# design.net
KiCad netlist of a schematic drawn in Altium Designer
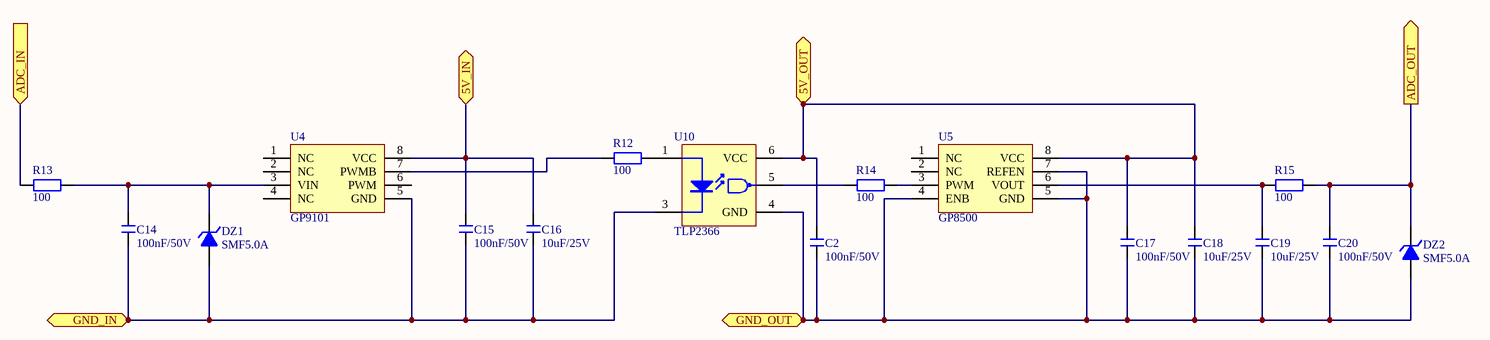
[diagram p0: 第一路电压隔离原理图.SchDoc]

(export (version "E")
  (design (tool "Eeschema 10.0.6"))
  (components
    (comp (ref "C2")
      (value "100nF/50V")
      (footprint "C 0603_M")
      (description "无极性贴片电容")
      (fields (field (name "版权归属") "源创客"))
      (libsource (lib "3.1   - 电阻-电容-电感") (part "C"))
    )
    (comp (ref "C14")
      (value "100nF/50V")
      (footprint "C 0603_M")
      (description "无极性贴片电容")
      (fields (field (name "版权归属") "源创客"))
      (libsource (lib "3.1   - 电阻-电容-电感") (part "C"))
    )
    (comp (ref "C15")
      (value "100nF/50V")
      (footprint "C 0603_M")
      (description "无极性贴片电容")
      (fields (field (name "版权归属") "源创客"))
      (libsource (lib "3.1   - 电阻-电容-电感") (part "C"))
    )
    (comp (ref "C16")
      (value "10uF/25V")
      (footprint "C 0603_M")
      (description "无极性贴片电容")
      (fields (field (name "版权归属") "源创客"))
      (libsource (lib "3.1   - 电阻-电容-电感") (part "C"))
    )
    (comp (ref "C17")
      (value "100nF/50V")
      (footprint "C 0603_M")
      (description "无极性贴片电容")
      (fields (field (name "版权归属") "源创客"))
      (libsource (lib "3.1   - 电阻-电容-电感") (part "C"))
    )
    (comp (ref "C18")
      (value "10uF/25V")
      (footprint "C 0603_M")
      (description "无极性贴片电容")
      (fields (field (name "版权归属") "源创客"))
      (libsource (lib "3.1   - 电阻-电容-电感") (part "C"))
    )
    (comp (ref "C19")
      (value "10uF/25V")
      (footprint "C 0603_M")
      (description "无极性贴片电容")
      (fields (field (name "版权归属") "源创客"))
      (libsource (lib "3.1   - 电阻-电容-电感") (part "C"))
    )
    (comp (ref "C20")
      (value "100nF/50V")
      (footprint "C 0603_M")
      (description "无极性贴片电容")
      (fields (field (name "版权归属") "源创客"))
      (libsource (lib "3.1   - 电阻-电容-电感") (part "C"))
    )
    (comp (ref "DZ1")
      (value "SMF5.0A")
      (footprint "SOD-123")
      (description "3.3V/0.5W稳压管")
      (fields (field (name "版权归属") "源创客"))
      (libsource (lib "8.1   - 二极管-整流桥") (part "1N4620"))
    )
    (comp (ref "DZ2")
      (value "SMF5.0A")
      (footprint "SOD-123")
      (description "3.3V/0.5W稳压管")
      (fields (field (name "版权归属") "源创客"))
      (libsource (lib "8.1   - 二极管-整流桥") (part "1N4620"))
    )
    (comp (ref "R12")
      (value "100")
      (footprint "R 0603_M")
      (description "贴片电阻")
      (fields (field (name "版权归属") "源创客"))
      (libsource (lib "3.1   - 电阻-电容-电感") (part "R"))
    )
    (comp (ref "R13")
      (value "100")
      (footprint "R 0603_M")
      (description "贴片电阻")
      (fields (field (name "版权归属") "源创客"))
      (libsource (lib "3.1   - 电阻-电容-电感") (part "R"))
    )
    (comp (ref "R14")
      (value "100")
      (footprint "R 0603_M")
      (description "贴片电阻")
      (fields (field (name "版权归属") "源创客"))
      (libsource (lib "3.1   - 电阻-电容-电感") (part "R"))
    )
    (comp (ref "R15")
      (value "100")
      (footprint "R 0603_M")
      (description "贴片电阻")
      (fields (field (name "版权归属") "源创客"))
      (libsource (lib "3.1   - 电阻-电容-电感") (part "R"))
    )
    (comp (ref "U4")
      (value "GP9101")
      (footprint "SOP8_N")
      (description "将0V到VCC的模拟电压输入，线性转换成0%-100%占  空比的PWM信号输出")
      (libsource (lib "1.1   - IC芯片") (part "GP9101"))
    )
    (comp (ref "U5")
      (value "GP8500")
      (footprint "SOP8_N")
      (description "0%-100% PWM 转 0-2.5V/0-VCC")
      (libsource (lib "1.1   - IC芯片") (part "GP8500"))
    )
    (comp (ref "U10")
      (value "TLP2366")
      (footprint "SOP5_N")
      (description "单路高速光耦")
      (libsource (lib "11.1 - 传感元件") (part "TLP2366"))
    )
  )
  (nets
    (net (code "1") (name "/5V_IN") (class "Default")
      (node (ref "C15") (pin "2") (pinfunction "2_2") (pintype "passive"))
      (node (ref "C16") (pin "2") (pinfunction "2_2") (pintype "passive"))
      (node (ref "U4") (pin "8") (pinfunction "VCC_8") (pintype "passive"))
    )
    (net (code "2") (name "/5V_OUT") (class "Default")
      (node (ref "C17") (pin "2") (pinfunction "2_2") (pintype "passive"))
      (node (ref "C18") (pin "2") (pinfunction "2_2") (pintype "passive"))
      (node (ref "C2") (pin "2") (pinfunction "2_2") (pintype "passive"))
      (node (ref "U10") (pin "6") (pinfunction "VCC_6") (pintype "passive"))
      (node (ref "U5") (pin "8") (pinfunction "VCC_8") (pintype "passive"))
    )
    (net (code "3") (name "/ADC_IN") (class "Default")
      (node (ref "R13") (pin "1") (pinfunction "1_1") (pintype "passive"))
    )
    (net (code "4") (name "/ADC_OUT") (class "Default")
      (node (ref "C20") (pin "2") (pinfunction "2_2") (pintype "passive"))
      (node (ref "DZ2") (pin "2") (pinfunction "K_2") (pintype "passive"))
      (node (ref "R15") (pin "2") (pinfunction "2_2") (pintype "passive"))
    )
    (net (code "5") (name "/GND_IN") (class "Default")
      (node (ref "C14") (pin "1") (pinfunction "1_1") (pintype "passive"))
      (node (ref "C15") (pin "1") (pinfunction "1_1") (pintype "passive"))
      (node (ref "C16") (pin "1") (pinfunction "1_1") (pintype "passive"))
      (node (ref "DZ1") (pin "1") (pinfunction "A_1") (pintype "passive"))
      (node (ref "U10") (pin "3") (pinfunction "LED-_3") (pintype "passive"))
      (node (ref "U4") (pin "5") (pinfunction "GND_5") (pintype "passive"))
    )
    (net (code "6") (name "/GND_OUT") (class "Default")
      (node (ref "C17") (pin "1") (pinfunction "1_1") (pintype "passive"))
      (node (ref "C18") (pin "1") (pinfunction "1_1") (pintype "passive"))
      (node (ref "C19") (pin "1") (pinfunction "1_1") (pintype "passive"))
      (node (ref "C2") (pin "1") (pinfunction "1_1") (pintype "passive"))
      (node (ref "C20") (pin "1") (pinfunction "1_1") (pintype "passive"))
      (node (ref "DZ2") (pin "1") (pinfunction "A_1") (pintype "passive"))
      (node (ref "U10") (pin "4") (pinfunction "GND_4") (pintype "passive"))
      (node (ref "U5") (pin "4") (pinfunction "ENB_4") (pintype "passive"))
      (node (ref "U5") (pin "5") (pinfunction "GND_5") (pintype "passive"))
      (node (ref "U5") (pin "7") (pinfunction "REFEN_7") (pintype "passive"))
    )
    (net (code "7") (name "Net-(DZ1-K)") (class "Default")
      (node (ref "C14") (pin "2") (pinfunction "2_2") (pintype "passive"))
      (node (ref "DZ1") (pin "2") (pinfunction "K_2") (pintype "passive"))
      (node (ref "R13") (pin "2") (pinfunction "2_2") (pintype "passive"))
      (node (ref "U4") (pin "3") (pinfunction "VIN_3") (pintype "passive"))
    )
    (net (code "8") (name "Net-(R14-Pad1)") (class "Default")
      (node (ref "R14") (pin "1") (pinfunction "1_1") (pintype "passive"))
      (node (ref "U10") (pin "5") (pinfunction "GND_5") (pintype "passive"))
    )
    (net (code "9") (name "Net-(U4-PWMB)") (class "Default")
      (node (ref "R12") (pin "1") (pinfunction "1_1") (pintype "passive"))
      (node (ref "U4") (pin "7") (pinfunction "PWMB_7") (pintype "passive"))
    )
    (net (code "10") (name "Net-(U5-PWM)") (class "Default")
      (node (ref "R14") (pin "2") (pinfunction "2_2") (pintype "passive"))
      (node (ref "U5") (pin "3") (pinfunction "PWM_3") (pintype "passive"))
    )
    (net (code "11") (name "Net-(U5-VOUT)") (class "Default")
      (node (ref "C19") (pin "2") (pinfunction "2_2") (pintype "passive"))
      (node (ref "R15") (pin "1") (pinfunction "1_1") (pintype "passive"))
      (node (ref "U5") (pin "6") (pinfunction "VOUT_6") (pintype "passive"))
    )
    (net (code "12") (name "Net-(U10-LED+)") (class "Default")
      (node (ref "R12") (pin "2") (pinfunction "2_2") (pintype "passive"))
      (node (ref "U10") (pin "1") (pinfunction "LED+_1") (pintype "passive"))
    )
    (net (code "13") (name "unconnected-(U4-NC-Pad1)") (class "Default")
      (node (ref "U4") (pin "1") (pinfunction "NC_1") (pintype "passive"))
    )
    (net (code "14") (name "unconnected-(U4-NC-Pad2)") (class "Default")
      (node (ref "U4") (pin "2") (pinfunction "NC_2") (pintype "passive"))
    )
    (net (code "15") (name "unconnected-(U4-NC-Pad4)") (class "Default")
      (node (ref "U4") (pin "4") (pinfunction "NC_4") (pintype "passive"))
    )
    (net (code "16") (name "unconnected-(U4-PWM-Pad6)") (class "Default")
      (node (ref "U4") (pin "6") (pinfunction "PWM_6") (pintype "passive"))
    )
    (net (code "17") (name "unconnected-(U5-NC-Pad1)") (class "Default")
      (node (ref "U5") (pin "1") (pinfunction "NC_1") (pintype "passive"))
    )
    (net (code "18") (name "unconnected-(U5-NC-Pad2)") (class "Default")
      (node (ref "U5") (pin "2") (pinfunction "NC_2") (pintype "passive"))
    )
  )
)
